# 1_BTB.net
KiCad netlist of a schematic drawn in Altium Designer
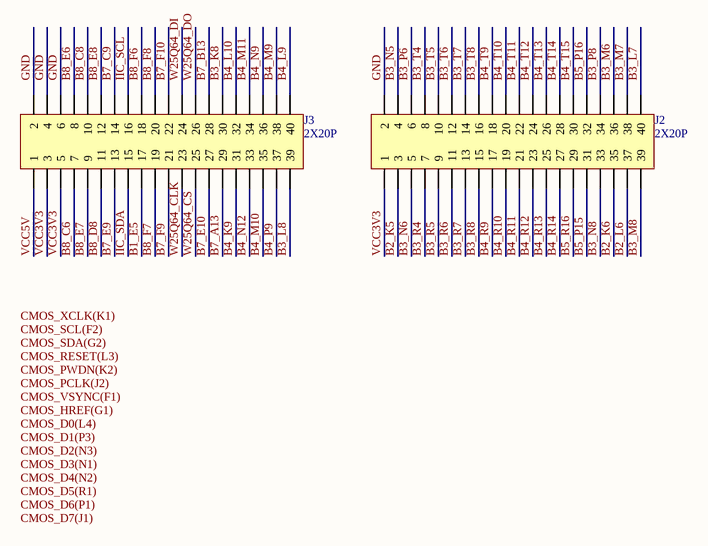
[diagram p0: 1_BTB.SchDoc]

(export (version "E")
  (design (tool "Eeschema 10.0.6"))
  (components
    (comp (ref "J2") (value "2X20P") (footprint "HEAD_2X20P") (libsource (lib "EP4CE6F17C8N") (part "2X20P")))
    (comp (ref "J3") (value "2X20P") (footprint "HEAD_2X20P") (libsource (lib "EP4CE6F17C8N") (part "2X20P")))
  )
  (nets
    (net (code "1") (name "/B1_E5") (class "Default")
      (node (ref "J3") (pin "17") (pinfunction "17_17") (pintype "passive"))
    )
    (net (code "2") (name "/B2_K5") (class "Default")
      (node (ref "J2") (pin "3") (pinfunction "3_3") (pintype "passive"))
    )
    (net (code "3") (name "/B2_K6") (class "Default")
      (node (ref "J2") (pin "35") (pinfunction "35_35") (pintype "passive"))
    )
    (net (code "4") (name "/B2_L6") (class "Default")
      (node (ref "J2") (pin "37") (pinfunction "37_37") (pintype "passive"))
    )
    (net (code "5") (name "/B3_K8") (class "Default")
      (node (ref "J3") (pin "30") (pinfunction "30_30") (pintype "passive"))
    )
    (net (code "6") (name "/B3_L7") (class "Default")
      (node (ref "J2") (pin "40") (pinfunction "40_40") (pintype "passive"))
    )
    (net (code "7") (name "/B3_L8") (class "Default")
      (node (ref "J3") (pin "39") (pinfunction "39_39") (pintype "passive"))
    )
    (net (code "8") (name "/B3_M6") (class "Default")
      (node (ref "J2") (pin "36") (pinfunction "36_36") (pintype "passive"))
    )
    (net (code "9") (name "/B3_M7") (class "Default")
      (node (ref "J2") (pin "38") (pinfunction "38_38") (pintype "passive"))
    )
    (net (code "10") (name "/B3_M8") (class "Default")
      (node (ref "J2") (pin "39") (pinfunction "39_39") (pintype "passive"))
    )
    (net (code "11") (name "/B3_N5") (class "Default")
      (node (ref "J2") (pin "4") (pinfunction "4_4") (pintype "passive"))
    )
    (net (code "12") (name "/B3_N6") (class "Default")
      (node (ref "J2") (pin "5") (pinfunction "5_5") (pintype "passive"))
    )
    (net (code "13") (name "/B3_N8") (class "Default")
      (node (ref "J2") (pin "33") (pinfunction "33_33") (pintype "passive"))
    )
    (net (code "14") (name "/B3_P6") (class "Default")
      (node (ref "J2") (pin "6") (pinfunction "6_6") (pintype "passive"))
    )
    (net (code "15") (name "/B3_P8") (class "Default")
      (node (ref "J2") (pin "34") (pinfunction "34_34") (pintype "passive"))
    )
    (net (code "16") (name "/B3_R4") (class "Default")
      (node (ref "J2") (pin "7") (pinfunction "7_7") (pintype "passive"))
    )
    (net (code "17") (name "/B3_R5") (class "Default")
      (node (ref "J2") (pin "9") (pinfunction "9_9") (pintype "passive"))
    )
    (net (code "18") (name "/B3_R6") (class "Default")
      (node (ref "J2") (pin "11") (pinfunction "11_11") (pintype "passive"))
    )
    (net (code "19") (name "/B3_R7") (class "Default")
      (node (ref "J2") (pin "13") (pinfunction "13_13") (pintype "passive"))
    )
    (net (code "20") (name "/B3_R8") (class "Default")
      (node (ref "J2") (pin "15") (pinfunction "15_15") (pintype "passive"))
    )
    (net (code "21") (name "/B3_T4") (class "Default")
      (node (ref "J2") (pin "8") (pinfunction "8_8") (pintype "passive"))
    )
    (net (code "22") (name "/B3_T5") (class "Default")
      (node (ref "J2") (pin "10") (pinfunction "10_10") (pintype "passive"))
    )
    (net (code "23") (name "/B3_T6") (class "Default")
      (node (ref "J2") (pin "12") (pinfunction "12_12") (pintype "passive"))
    )
    (net (code "24") (name "/B3_T7") (class "Default")
      (node (ref "J2") (pin "14") (pinfunction "14_14") (pintype "passive"))
    )
    (net (code "25") (name "/B3_T8") (class "Default")
      (node (ref "J2") (pin "16") (pinfunction "16_16") (pintype "passive"))
    )
    (net (code "26") (name "/B4_K9") (class "Default")
      (node (ref "J3") (pin "31") (pinfunction "31_31") (pintype "passive"))
    )
    (net (code "27") (name "/B4_L9") (class "Default")
      (node (ref "J3") (pin "40") (pinfunction "40_40") (pintype "passive"))
    )
    (net (code "28") (name "/B4_L10") (class "Default")
      (node (ref "J3") (pin "32") (pinfunction "32_32") (pintype "passive"))
    )
    (net (code "29") (name "/B4_M9") (class "Default")
      (node (ref "J3") (pin "38") (pinfunction "38_38") (pintype "passive"))
    )
    (net (code "30") (name "/B4_M10") (class "Default")
      (node (ref "J3") (pin "35") (pinfunction "35_35") (pintype "passive"))
    )
    (net (code "31") (name "/B4_M11") (class "Default")
      (node (ref "J3") (pin "34") (pinfunction "34_34") (pintype "passive"))
    )
    (net (code "32") (name "/B4_N9") (class "Default")
      (node (ref "J3") (pin "36") (pinfunction "36_36") (pintype "passive"))
    )
    (net (code "33") (name "/B4_N12") (class "Default")
      (node (ref "J3") (pin "33") (pinfunction "33_33") (pintype "passive"))
    )
    (net (code "34") (name "/B4_P9") (class "Default")
      (node (ref "J3") (pin "37") (pinfunction "37_37") (pintype "passive"))
    )
    (net (code "35") (name "/B4_R9") (class "Default")
      (node (ref "J2") (pin "17") (pinfunction "17_17") (pintype "passive"))
    )
    (net (code "36") (name "/B4_R10") (class "Default")
      (node (ref "J2") (pin "19") (pinfunction "19_19") (pintype "passive"))
    )
    (net (code "37") (name "/B4_R11") (class "Default")
      (node (ref "J2") (pin "21") (pinfunction "21_21") (pintype "passive"))
    )
    (net (code "38") (name "/B4_R12") (class "Default")
      (node (ref "J2") (pin "23") (pinfunction "23_23") (pintype "passive"))
    )
    (net (code "39") (name "/B4_R13") (class "Default")
      (node (ref "J2") (pin "25") (pinfunction "25_25") (pintype "passive"))
    )
    (net (code "40") (name "/B4_R14") (class "Default")
      (node (ref "J2") (pin "27") (pinfunction "27_27") (pintype "passive"))
    )
    (net (code "41") (name "/B4_T9") (class "Default")
      (node (ref "J2") (pin "18") (pinfunction "18_18") (pintype "passive"))
    )
    (net (code "42") (name "/B4_T10") (class "Default")
      (node (ref "J2") (pin "20") (pinfunction "20_20") (pintype "passive"))
    )
    (net (code "43") (name "/B4_T11") (class "Default")
      (node (ref "J2") (pin "22") (pinfunction "22_22") (pintype "passive"))
    )
    (net (code "44") (name "/B4_T12") (class "Default")
      (node (ref "J2") (pin "24") (pinfunction "24_24") (pintype "passive"))
    )
    (net (code "45") (name "/B4_T13") (class "Default")
      (node (ref "J2") (pin "26") (pinfunction "26_26") (pintype "passive"))
    )
    (net (code "46") (name "/B4_T14") (class "Default")
      (node (ref "J2") (pin "28") (pinfunction "28_28") (pintype "passive"))
    )
    (net (code "47") (name "/B4_T15") (class "Default")
      (node (ref "J2") (pin "30") (pinfunction "30_30") (pintype "passive"))
    )
    (net (code "48") (name "/B5_P15") (class "Default")
      (node (ref "J2") (pin "31") (pinfunction "31_31") (pintype "passive"))
    )
    (net (code "49") (name "/B5_P16") (class "Default")
      (node (ref "J2") (pin "32") (pinfunction "32_32") (pintype "passive"))
    )
    (net (code "50") (name "/B5_R16") (class "Default")
      (node (ref "J2") (pin "29") (pinfunction "29_29") (pintype "passive"))
    )
    (net (code "51") (name "/B7_A13") (class "Default")
      (node (ref "J3") (pin "29") (pinfunction "29_29") (pintype "passive"))
    )
    (net (code "52") (name "/B7_B13") (class "Default")
      (node (ref "J3") (pin "28") (pinfunction "28_28") (pintype "passive"))
    )
    (net (code "53") (name "/B7_C9") (class "Default")
      (node (ref "J3") (pin "14") (pinfunction "14_14") (pintype "passive"))
    )
    (net (code "54") (name "/B7_E9") (class "Default")
      (node (ref "J3") (pin "13") (pinfunction "13_13") (pintype "passive"))
    )
    (net (code "55") (name "/B7_E10") (class "Default")
      (node (ref "J3") (pin "27") (pinfunction "27_27") (pintype "passive"))
    )
    (net (code "56") (name "/B7_F9") (class "Default")
      (node (ref "J3") (pin "21") (pinfunction "21_21") (pintype "passive"))
    )
    (net (code "57") (name "/B7_F10") (class "Default")
      (node (ref "J3") (pin "22") (pinfunction "22_22") (pintype "passive"))
    )
    (net (code "58") (name "/B8_C6") (class "Default")
      (node (ref "J3") (pin "7") (pinfunction "7_7") (pintype "passive"))
    )
    (net (code "59") (name "/B8_C8") (class "Default")
      (node (ref "J3") (pin "10") (pinfunction "10_10") (pintype "passive"))
    )
    (net (code "60") (name "/B8_D8") (class "Default")
      (node (ref "J3") (pin "11") (pinfunction "11_11") (pintype "passive"))
    )
    (net (code "61") (name "/B8_E6") (class "Default")
      (node (ref "J3") (pin "8") (pinfunction "8_8") (pintype "passive"))
    )
    (net (code "62") (name "/B8_E7") (class "Default")
      (node (ref "J3") (pin "9") (pinfunction "9_9") (pintype "passive"))
    )
    (net (code "63") (name "/B8_E8") (class "Default")
      (node (ref "J3") (pin "12") (pinfunction "12_12") (pintype "passive"))
    )
    (net (code "64") (name "/B8_F6") (class "Default")
      (node (ref "J3") (pin "18") (pinfunction "18_18") (pintype "passive"))
    )
    (net (code "65") (name "/B8_F7") (class "Default")
      (node (ref "J3") (pin "19") (pinfunction "19_19") (pintype "passive"))
    )
    (net (code "66") (name "/B8_F8") (class "Default")
      (node (ref "J3") (pin "20") (pinfunction "20_20") (pintype "passive"))
    )
    (net (code "83") (name "/GND") (class "Default")
      (node (ref "J2") (pin "2") (pinfunction "2_2") (pintype "passive"))
      (node (ref "J3") (pin "2") (pinfunction "2_2") (pintype "passive"))
      (node (ref "J3") (pin "4") (pinfunction "4_4") (pintype "passive"))
      (node (ref "J3") (pin "6") (pinfunction "6_6") (pintype "passive"))
    )
    (net (code "84") (name "/IIC_SCL") (class "Default")
      (node (ref "J3") (pin "16") (pinfunction "16_16") (pintype "passive"))
    )
    (net (code "85") (name "/IIC_SDA") (class "Default")
      (node (ref "J3") (pin "15") (pinfunction "15_15") (pintype "passive"))
    )
    (net (code "86") (name "/VCC3V3") (class "Default")
      (node (ref "J2") (pin "1") (pinfunction "1_1") (pintype "passive"))
      (node (ref "J3") (pin "3") (pinfunction "3_3") (pintype "passive"))
      (node (ref "J3") (pin "5") (pinfunction "5_5") (pintype "passive"))
    )
    (net (code "87") (name "/VCC5V") (class "Default")
      (node (ref "J3") (pin "1") (pinfunction "1_1") (pintype "passive"))
    )
    (net (code "88") (name "/W25Q64_CLK") (class "Default")
      (node (ref "J3") (pin "23") (pinfunction "23_23") (pintype "passive"))
    )
    (net (code "89") (name "/W25Q64_CS") (class "Default")
      (node (ref "J3") (pin "25") (pinfunction "25_25") (pintype "passive"))
    )
    (net (code "90") (name "/W25Q64_DI") (class "Default")
      (node (ref "J3") (pin "24") (pinfunction "24_24") (pintype "passive"))
    )
    (net (code "91") (name "/W25Q64_DO") (class "Default")
      (node (ref "J3") (pin "26") (pinfunction "26_26") (pintype "passive"))
    )
  )
)
